# EPS_5V_EMI-Filter_In.net
KiCad netlist of a schematic drawn in Altium Designer
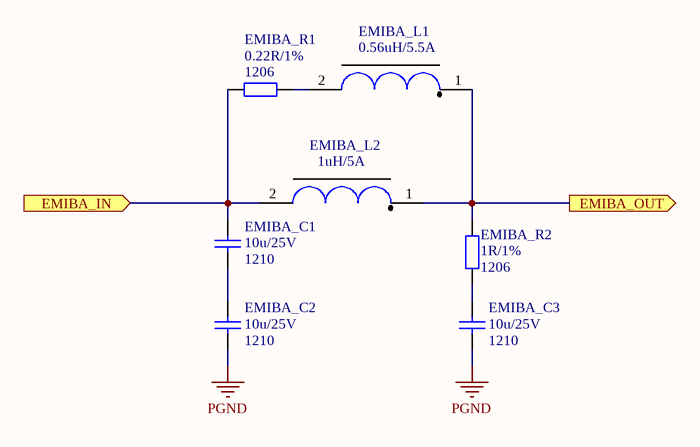
[diagram p0: EPS_5V_EMI-Filter_In.SchDoc]

(export (version "E")
  (design (tool "Eeschema 10.0.6"))
  (components
    (comp (ref "EMIBA_C1")
      (value "10u/25V")
      (footprint "SMD_Capacitor_1210")
      (description "Ceramic Cap Murata Automotive 10u/25V X7R 1210")
      (fields
        (field (name "MANUFACTURER") "Murata")
        (field (name "MANUFACTURERPARTNUMBER") "GCJ32ER71E106KA12L")
        (field (name "PACKAGE") "1210")
      )
      (libsource (lib "capacitors") (part "Cer_GCJ32ER71E106KA12L"))
    )
    (comp (ref "EMIBA_C2")
      (value "10u/25V")
      (footprint "SMD_Capacitor_1210")
      (description "Ceramic Cap Murata Automotive 10u/25V X7R 1210")
      (fields
        (field (name "MANUFACTURER") "Murata")
        (field (name "MANUFACTURERPARTNUMBER") "GCJ32ER71E106KA12L")
        (field (name "PACKAGE") "1210")
      )
      (libsource (lib "capacitors") (part "Cer_GCJ32ER71E106KA12L"))
    )
    (comp (ref "EMIBA_C3")
      (value "10u/25V")
      (footprint "SMD_Capacitor_1210")
      (description "Ceramic Cap Murata Automotive 10u/25V X7R 1210")
      (fields
        (field (name "MANUFACTURER") "Murata")
        (field (name "MANUFACTURERPARTNUMBER") "GCJ32ER71E106KA12L")
        (field (name "PACKAGE") "1210")
      )
      (libsource (lib "capacitors") (part "Cer_GCJ32ER71E106KA12L"))
    )
    (comp (ref "EMIBA_L1")
      (value "0.56uH/5.5A")
      (footprint "Vishay_IHLP1212")
      (description "Vishay IHLP1212 Inductor, L=0.56uH, Irise40deg=5.5A, ESR=16mR, SRF=1MHz.")
      (fields
        (field (name "MANUFACTURER") "Vishay")
        (field (name "MANUFACTURERPARTNUMBER") "IHLP1212BZERR56M11")
      )
      (libsource (lib "inductors") (part "IHLP1212BZERR56M11"))
    )
    (comp (ref "EMIBA_L2")
      (value "1uH/5A")
      (footprint "Vishay_IHLP1212")
      (description "Vishay IHLP1212 Inductor, L=1uH, Irise40deg=5A, ESR=20mR, SRF=1MHz.")
      (fields
        (field (name "MANUFACTURER") "Vishay")
        (field (name "MANUFACTURERPARTNUMBER") "IHLP1212BZER1R0M11")
      )
      (libsource (lib "inductors") (part "IHLP1212BZER1R0M11"))
    )
    (comp (ref "EMIBA_R1")
      (value "0.22R/1%")
      (footprint "SMD_Resistor_1206")
      (description "Panasonic Resistor 0.22R 1% 1206 330mW")
      (fields
        (field (name "MANUFACTURER") "Panasonic")
        (field (name "MANUFACTURERPARTNUMBER") "ERJ-8BQFR22V")
        (field (name "PACKAGE") "1206")
      )
      (libsource (lib "resistors") (part "ERJ-8BQFR22V"))
    )
    (comp (ref "EMIBA_R2")
      (value "1R/1%")
      (footprint "SMD_Resistor_1206")
      (description "Panasonic Resistor 1R 1% 1206 330mW")
      (fields
        (field (name "MANUFACTURERPARTNUMBER") "ERJ-8BQF1R0V")
        (field (name "MANUFACTURER") "Panasonic")
        (field (name "PACKAGE") "1206")
      )
      (libsource (lib "resistors") (part "ERJ-8BQF1R0V"))
    )
  )
  (nets
    (net (code "1") (name "/EMIBA_IN") (class "Default")
      (node (ref "EMIBA_C1") (pin "1") (pinfunction "1_1") (pintype "passive"))
      (node (ref "EMIBA_L2") (pin "2") (pinfunction "2_2") (pintype "passive"))
      (node (ref "EMIBA_R1") (pin "1") (pinfunction "1_1") (pintype "passive"))
    )
    (net (code "2") (name "/EMIBA_OUT") (class "Default")
      (node (ref "EMIBA_L1") (pin "1") (pinfunction "1_1") (pintype "passive"))
      (node (ref "EMIBA_L2") (pin "1") (pinfunction "1_1") (pintype "passive"))
      (node (ref "EMIBA_R2") (pin "2") (pinfunction "2_2") (pintype "passive"))
    )
    (net (code "3") (name "Net-(EMIBA_C1-Pad2)") (class "Default")
      (node (ref "EMIBA_C1") (pin "2") (pinfunction "2_2") (pintype "passive"))
      (node (ref "EMIBA_C2") (pin "1") (pinfunction "1_1") (pintype "passive"))
    )
    (net (code "4") (name "Net-(EMIBA_C3-Pad1)") (class "Default")
      (node (ref "EMIBA_C3") (pin "1") (pinfunction "1_1") (pintype "passive"))
      (node (ref "EMIBA_R2") (pin "1") (pinfunction "1_1") (pintype "passive"))
    )
    (net (code "5") (name "Net-(EMIBA_L1-Pad2)") (class "Default")
      (node (ref "EMIBA_L1") (pin "2") (pinfunction "2_2") (pintype "passive"))
      (node (ref "EMIBA_R1") (pin "2") (pinfunction "2_2") (pintype "passive"))
    )
    (net (code "6") (name "PGND") (class "Default")
      (node (ref "EMIBA_C2") (pin "2") (pinfunction "2_2") (pintype "passive"))
      (node (ref "EMIBA_C3") (pin "2") (pinfunction "2_2") (pintype "passive"))
    )
  )
)
